# SCH_keyboard_ProMicro_2025-01-13.net
KiCad netlist of a schematic drawn in EasyEDA
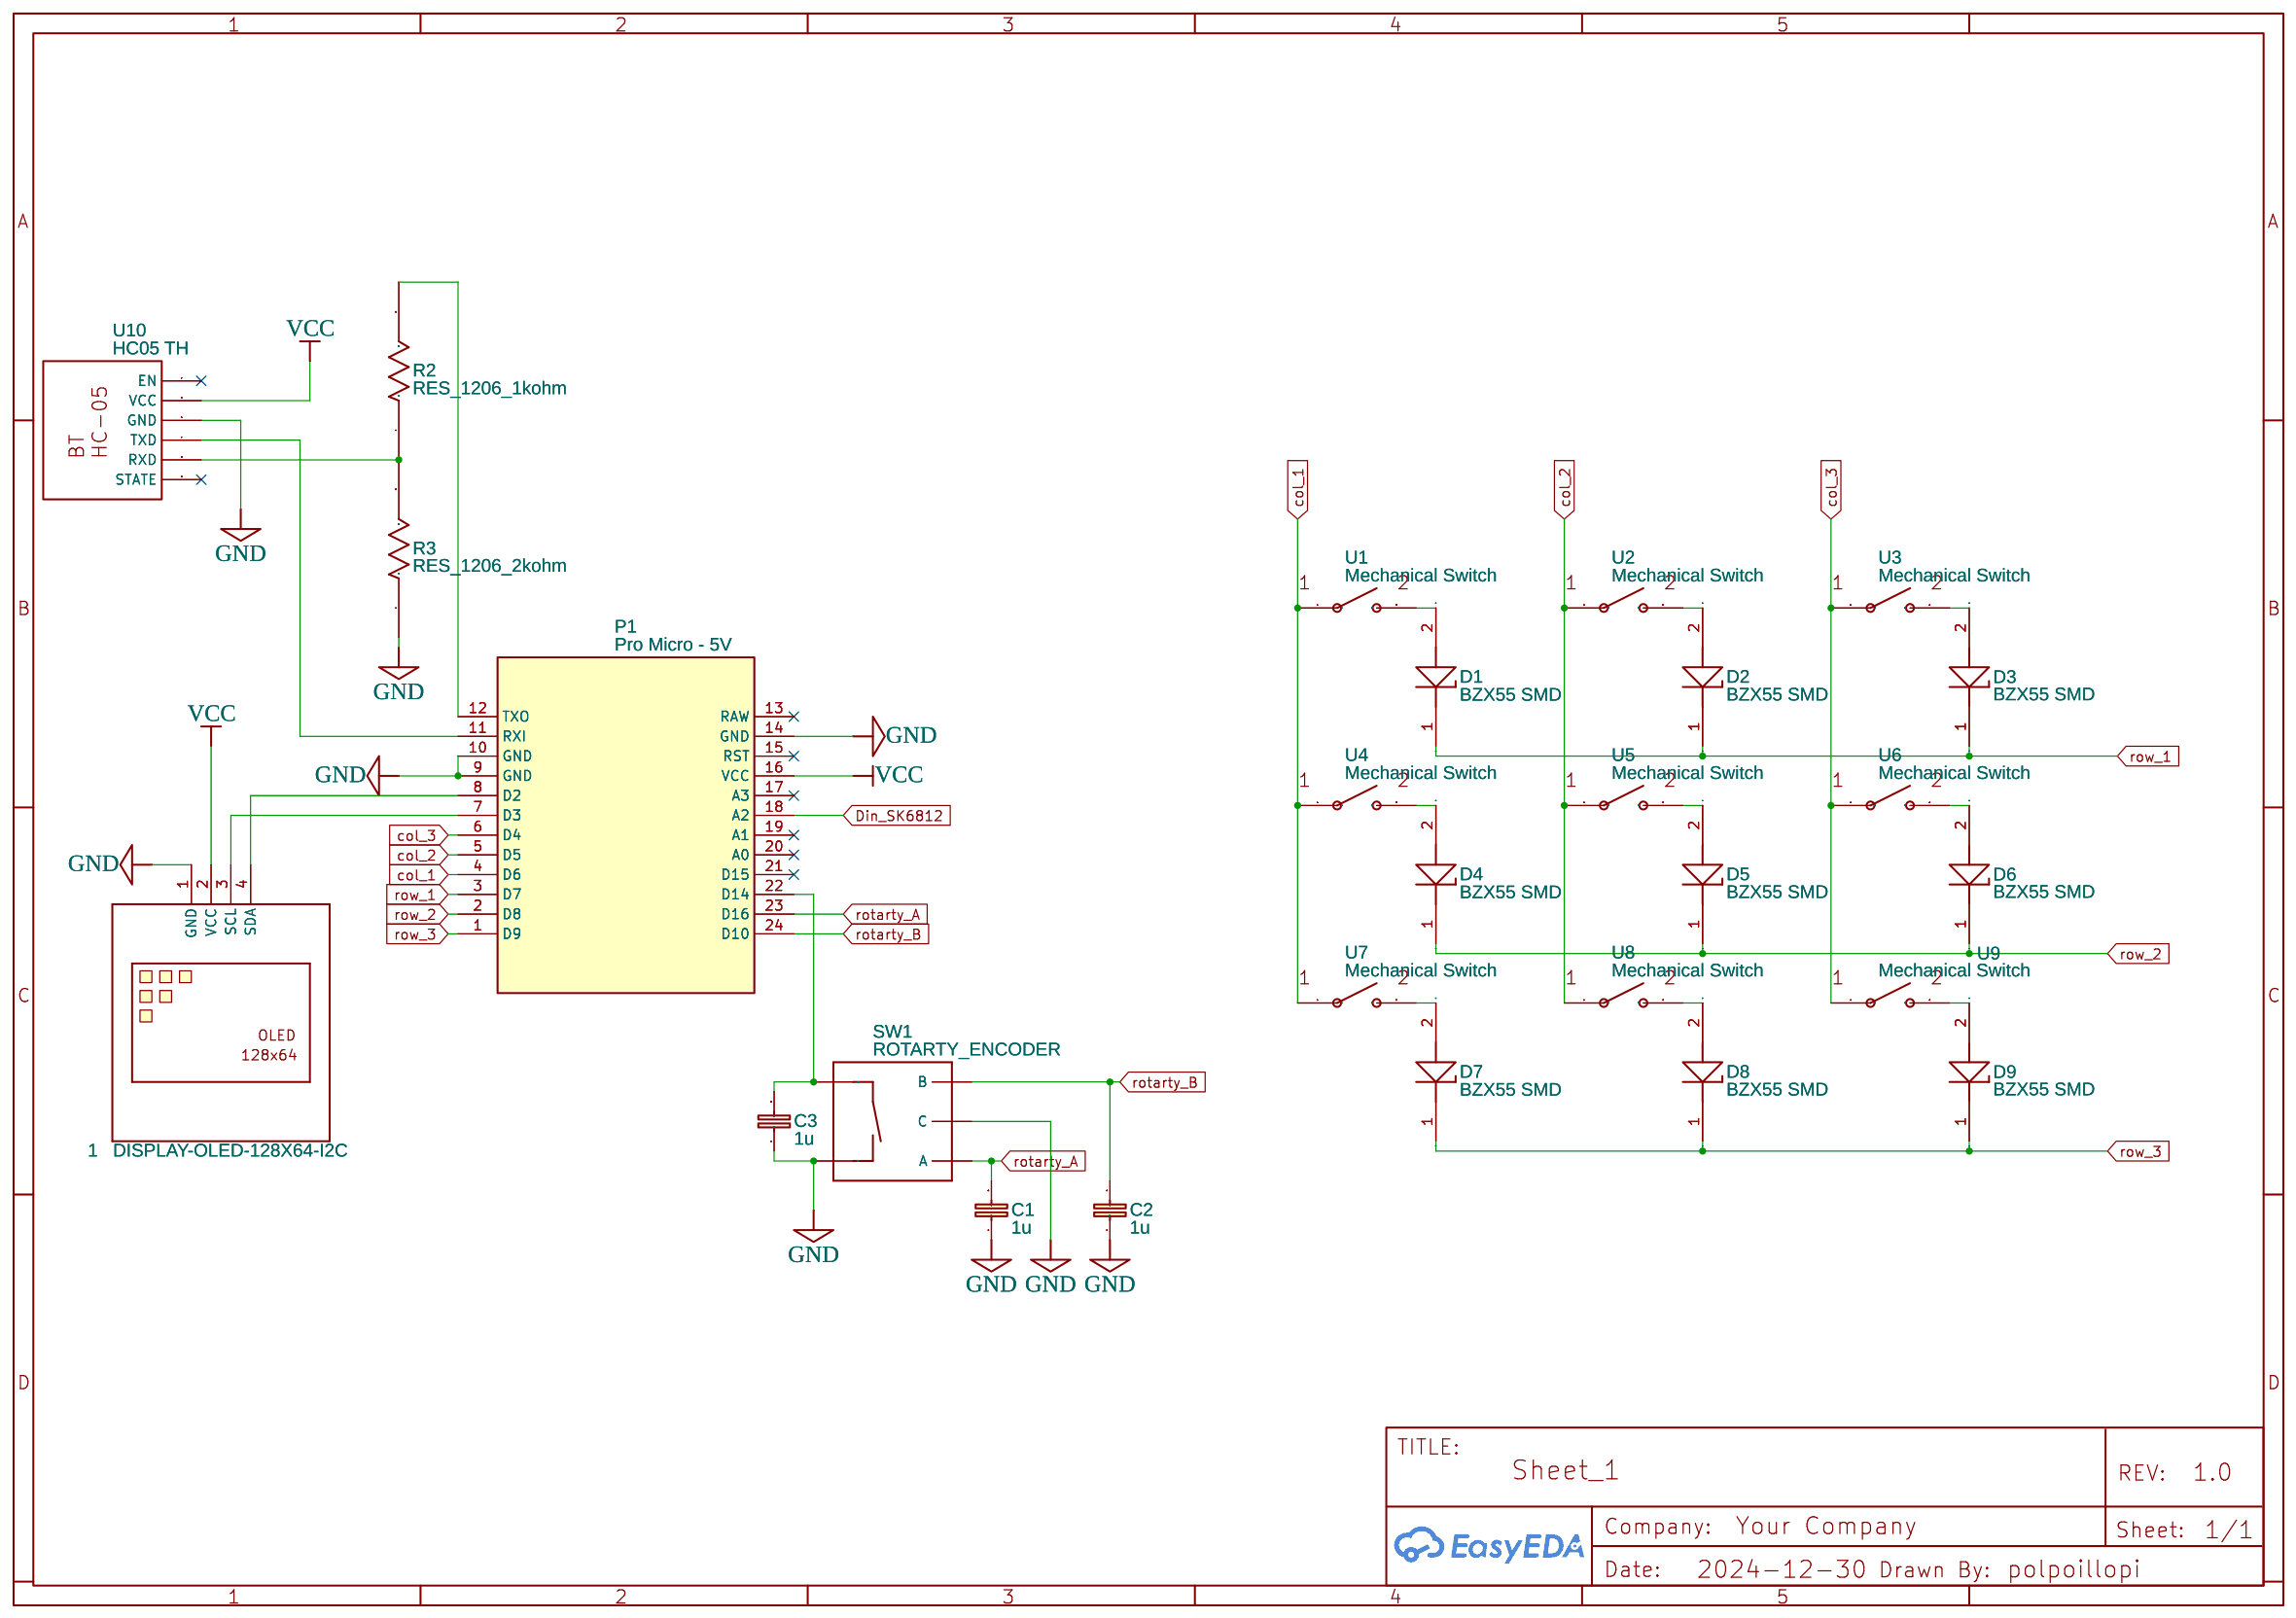
[diagram p0: Sheet_1]
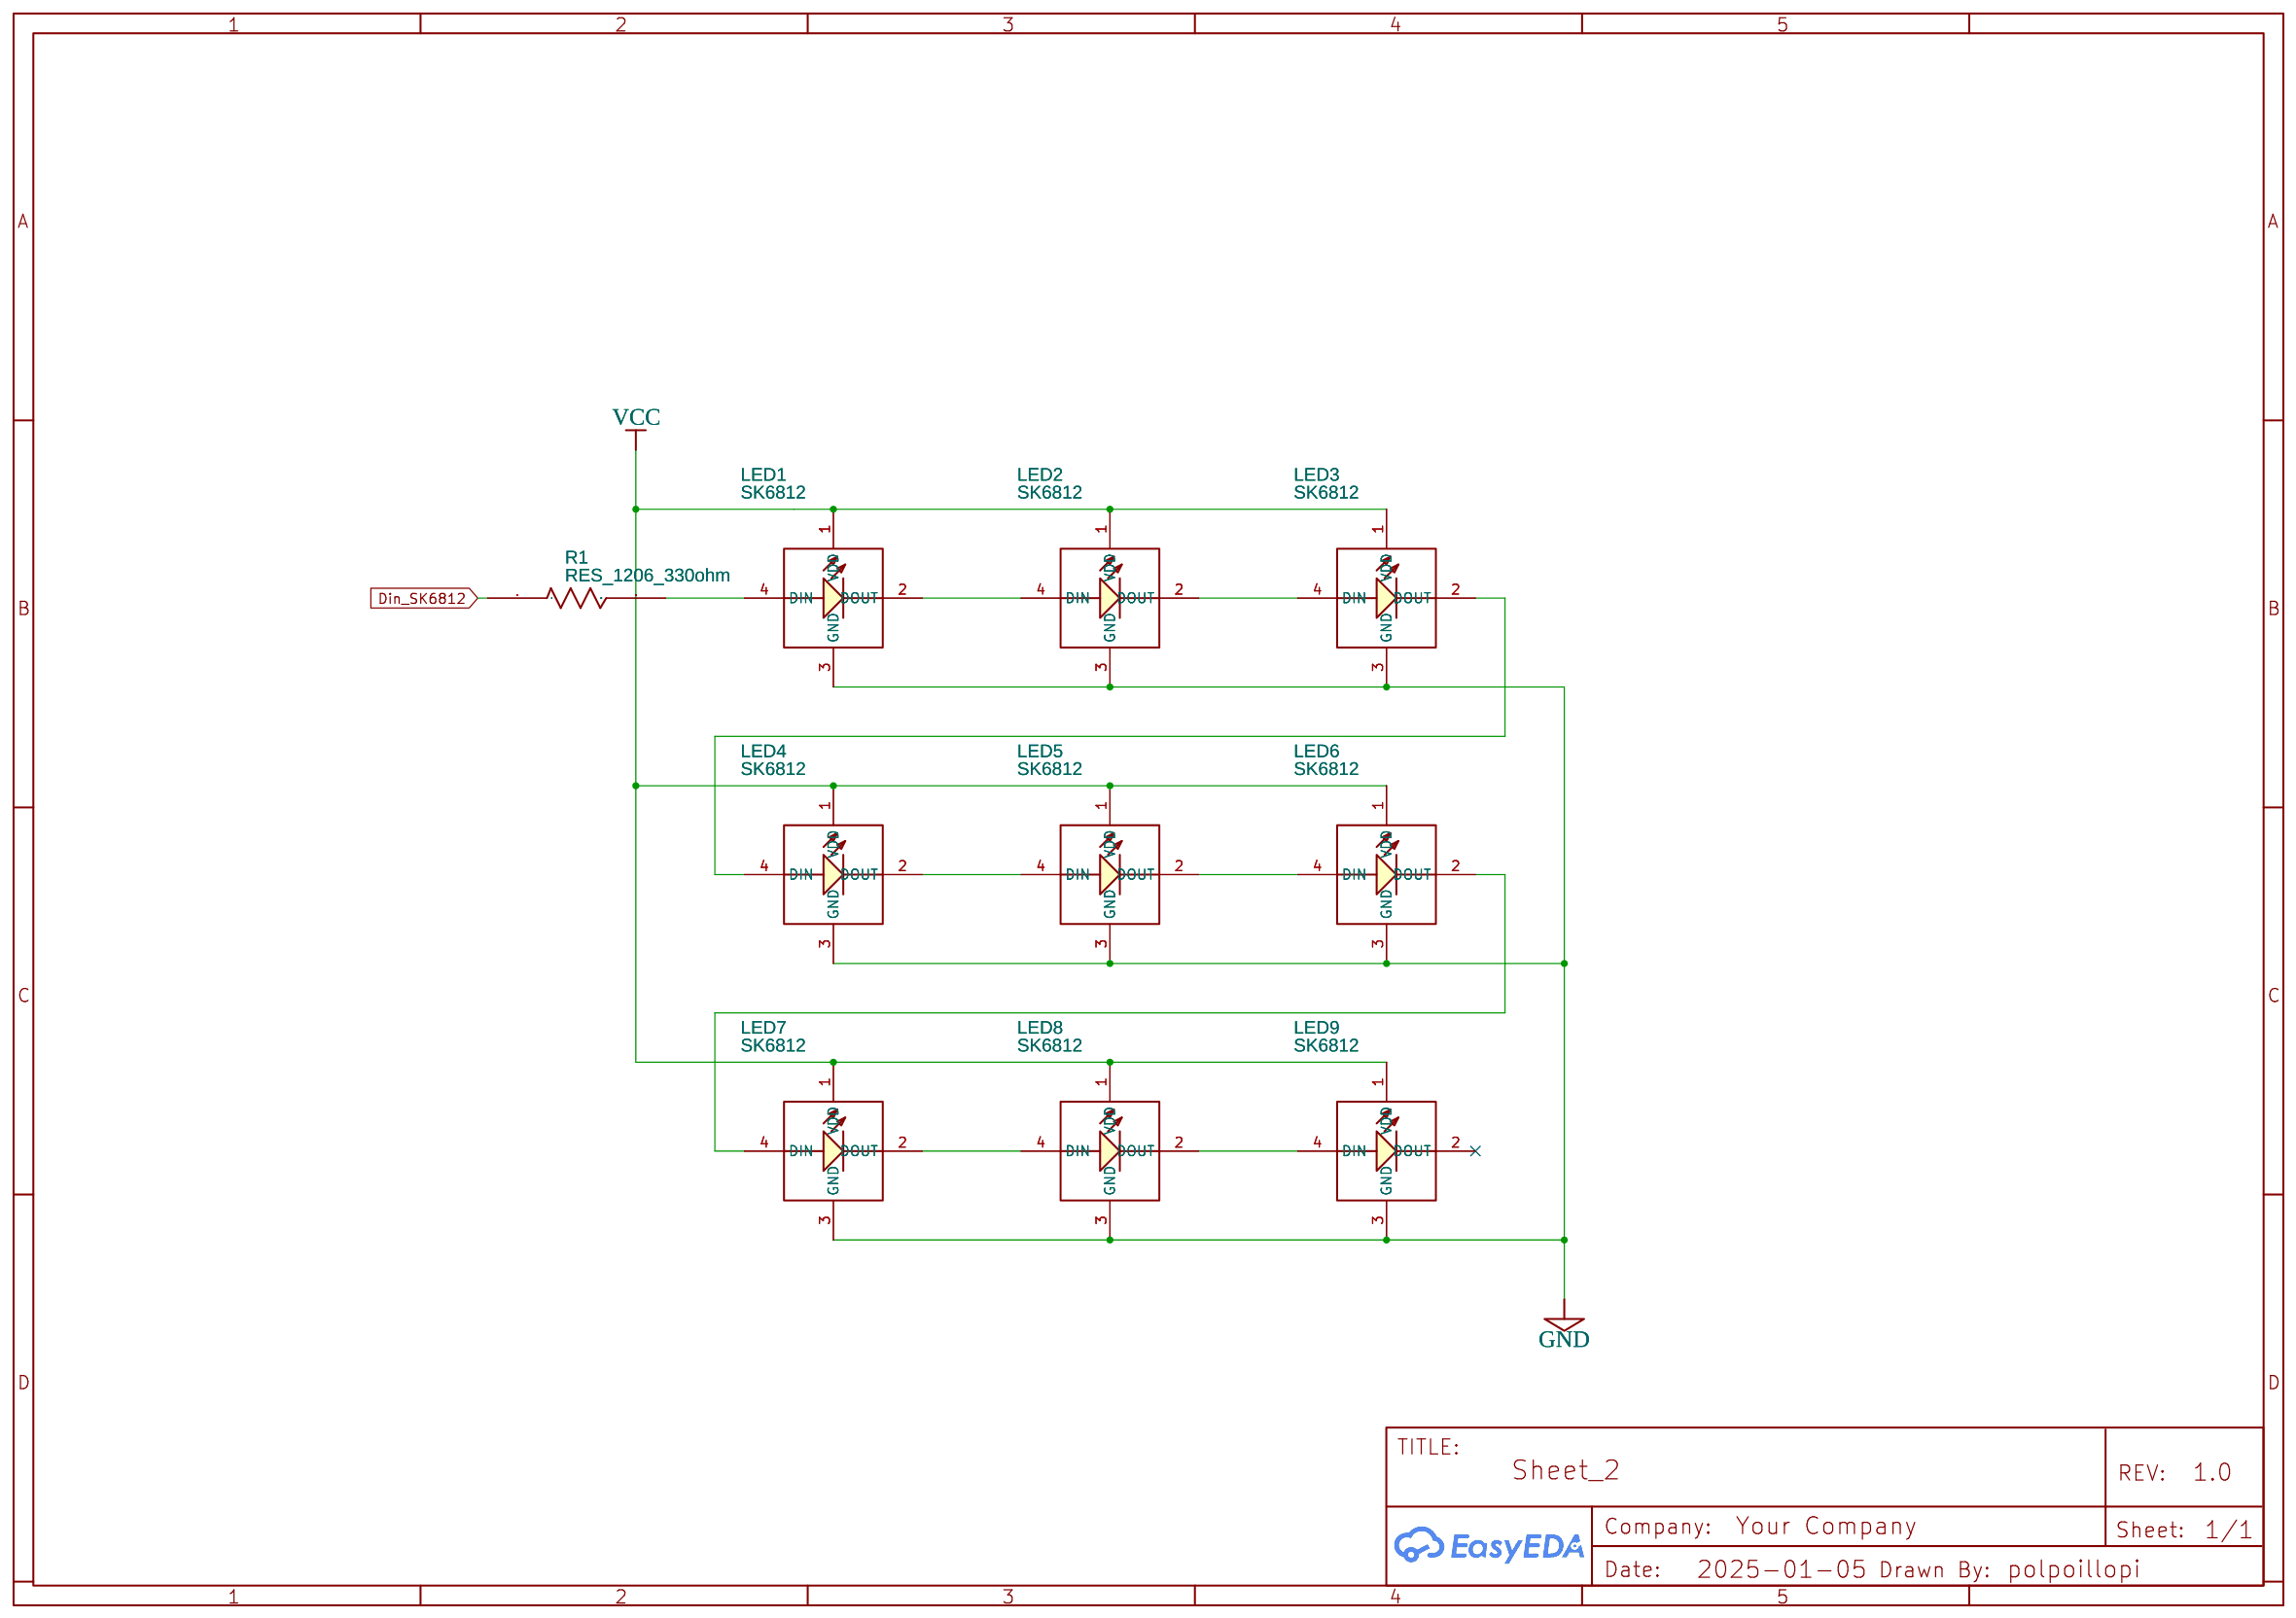
[diagram p1: Sheet_2]

(export (version "E")
  (design (tool "Eeschema 10.0.6"))
  (components
    (comp (ref "1") (value "DISPLAY-OLED-128X64-I2C") (libsource (lib "") (part "DISPLAY-OLED-128X64-I2C")))
    (comp (ref "C1") (value "1u") (libsource (lib "") (part "CAP1206")))
    (comp (ref "C2") (value "1u") (libsource (lib "") (part "CAP1206")))
    (comp (ref "C3") (value "1u") (libsource (lib "") (part "CAP1206")))
    (comp (ref "D1") (value "BZX55 SMD") (libsource (lib "") (part "BZX55 SMD")))
    (comp (ref "D2") (value "BZX55 SMD") (libsource (lib "") (part "BZX55 SMD")))
    (comp (ref "D3") (value "BZX55 SMD") (libsource (lib "") (part "BZX55 SMD")))
    (comp (ref "D4") (value "BZX55 SMD") (libsource (lib "") (part "BZX55 SMD")))
    (comp (ref "D5") (value "BZX55 SMD") (libsource (lib "") (part "BZX55 SMD")))
    (comp (ref "D6") (value "BZX55 SMD") (libsource (lib "") (part "BZX55 SMD")))
    (comp (ref "D7") (value "BZX55 SMD") (libsource (lib "") (part "BZX55 SMD")))
    (comp (ref "D8") (value "BZX55 SMD") (libsource (lib "") (part "BZX55 SMD")))
    (comp (ref "D9") (value "BZX55 SMD") (libsource (lib "") (part "BZX55 SMD")))
    (comp (ref "P1") (value "Pro Micro - 5V") (libsource (lib "") (part "Pro Micro - 5V")))
    (comp (ref "R2")
      (value "RES_1206_1kohm")
      (fields (field (name "Manufacturer") "Panasonic"))
      (libsource (lib "") (part "RES_1206_330K_5%"))
    )
    (comp (ref "R3")
      (value "RES_1206_2kohm")
      (fields (field (name "Manufacturer") "Panasonic"))
      (libsource (lib "") (part "RES_1206_330K_5%"))
    )
    (comp (ref "SW1") (value "ROTARTY_ENCODER") (libsource (lib "") (part "ROTARTY_ENCODER")))
    (comp (ref "U1")
      (value "Mechanical Switch")
      (libsource (lib "") (part "Cherry MX Mechanical Keyboard Switch"))
    )
    (comp (ref "U2")
      (value "Mechanical Switch")
      (libsource (lib "") (part "Cherry MX Mechanical Keyboard Switch"))
    )
    (comp (ref "U3")
      (value "Mechanical Switch")
      (libsource (lib "") (part "Cherry MX Mechanical Keyboard Switch"))
    )
    (comp (ref "U4")
      (value "Mechanical Switch")
      (libsource (lib "") (part "Cherry MX Mechanical Keyboard Switch"))
    )
    (comp (ref "U5")
      (value "Mechanical Switch")
      (libsource (lib "") (part "Cherry MX Mechanical Keyboard Switch"))
    )
    (comp (ref "U6")
      (value "Mechanical Switch")
      (libsource (lib "") (part "Cherry MX Mechanical Keyboard Switch"))
    )
    (comp (ref "U7")
      (value "Mechanical Switch")
      (libsource (lib "") (part "Cherry MX Mechanical Keyboard Switch"))
    )
    (comp (ref "U8")
      (value "Mechanical Switch")
      (libsource (lib "") (part "Cherry MX Mechanical Keyboard Switch"))
    )
    (comp (ref "U9")
      (value "Mechanical Switch")
      (libsource (lib "") (part "Cherry MX Mechanical Keyboard Switch"))
    )
    (comp (ref "U10") (value "HC05 TH") (libsource (lib "") (part "HC05 TH")))
    (comp (ref "LED1") (value "SK6812") (libsource (lib "") (part "SK6812")))
    (comp (ref "LED2") (value "SK6812") (libsource (lib "") (part "SK6812")))
    (comp (ref "LED3") (value "SK6812") (libsource (lib "") (part "SK6812")))
    (comp (ref "LED4") (value "SK6812") (libsource (lib "") (part "SK6812")))
    (comp (ref "LED5") (value "SK6812") (libsource (lib "") (part "SK6812")))
    (comp (ref "LED6") (value "SK6812") (libsource (lib "") (part "SK6812")))
    (comp (ref "LED7") (value "SK6812") (libsource (lib "") (part "SK6812")))
    (comp (ref "LED8") (value "SK6812") (libsource (lib "") (part "SK6812")))
    (comp (ref "LED9") (value "SK6812") (libsource (lib "") (part "SK6812")))
    (comp (ref "R1")
      (value "RES_1206_330ohm")
      (fields (field (name "Manufacturer") "Panasonic"))
      (libsource (lib "") (part "RES_1206_330K_5%"))
    )
  )
  (nets
    (net (code "1") (name "Din_SK6812") (class "Default")
      (node (ref "P1") (pin "18") (pinfunction "A2_18") (pintype "unspecified"))
      (node (ref "R1") (pin "A") (pinfunction "A_A") (pintype "unspecified"))
    )
    (net (code "2") (name "GND") (class "Default")
      (node (ref "1") (pin "1") (pinfunction "GND_1") (pintype "bidirectional"))
      (node (ref "C1") (pin "1") (pinfunction "1_1") (pintype "unspecified"))
      (node (ref "C2") (pin "1") (pinfunction "1_1") (pintype "unspecified"))
      (node (ref "C3") (pin "1") (pinfunction "1_1") (pintype "unspecified"))
      (node (ref "LED1") (pin "3") (pinfunction "GND_3") (pintype "unspecified"))
      (node (ref "LED2") (pin "3") (pinfunction "GND_3") (pintype "unspecified"))
      (node (ref "LED3") (pin "3") (pinfunction "GND_3") (pintype "unspecified"))
      (node (ref "LED4") (pin "3") (pinfunction "GND_3") (pintype "unspecified"))
      (node (ref "LED5") (pin "3") (pinfunction "GND_3") (pintype "unspecified"))
      (node (ref "LED6") (pin "3") (pinfunction "GND_3") (pintype "unspecified"))
      (node (ref "LED7") (pin "3") (pinfunction "GND_3") (pintype "unspecified"))
      (node (ref "LED8") (pin "3") (pinfunction "GND_3") (pintype "unspecified"))
      (node (ref "LED9") (pin "3") (pinfunction "GND_3") (pintype "unspecified"))
      (node (ref "P1") (pin "10") (pinfunction "GND_10") (pintype "unspecified"))
      (node (ref "P1") (pin "14") (pinfunction "GND_14") (pintype "unspecified"))
      (node (ref "P1") (pin "9") (pinfunction "GND_9") (pintype "unspecified"))
      (node (ref "R3") (pin "A") (pinfunction "A_A") (pintype "unspecified"))
      (node (ref "SW1") (pin "2") (pinfunction "C_2") (pintype "unspecified"))
      (node (ref "SW1") (pin "5") (pinfunction "SW-_5") (pintype "unspecified"))
      (node (ref "U10") (pin "3") (pinfunction "GND_3") (pintype "unspecified"))
    )
    (net (code "3") (name "Net-(1-SCL)") (class "Default")
      (node (ref "1") (pin "3") (pinfunction "SCL_3") (pintype "bidirectional"))
      (node (ref "P1") (pin "7") (pinfunction "D3_7") (pintype "unspecified"))
    )
    (net (code "4") (name "Net-(1-SDA)") (class "Default")
      (node (ref "1") (pin "4") (pinfunction "SDA_4") (pintype "bidirectional"))
      (node (ref "P1") (pin "8") (pinfunction "D2_8") (pintype "unspecified"))
    )
    (net (code "5") (name "Net-(D1-K)") (class "Default")
      (node (ref "D1") (pin "2") (pinfunction "K_2") (pintype "unspecified"))
      (node (ref "U1") (pin "2") (pinfunction "2_2") (pintype "unspecified"))
    )
    (net (code "6") (name "Net-(D2-K)") (class "Default")
      (node (ref "D2") (pin "2") (pinfunction "K_2") (pintype "unspecified"))
      (node (ref "U2") (pin "2") (pinfunction "2_2") (pintype "unspecified"))
    )
    (net (code "7") (name "Net-(D3-K)") (class "Default")
      (node (ref "D3") (pin "2") (pinfunction "K_2") (pintype "unspecified"))
      (node (ref "U3") (pin "2") (pinfunction "2_2") (pintype "unspecified"))
    )
    (net (code "8") (name "Net-(D4-K)") (class "Default")
      (node (ref "D4") (pin "2") (pinfunction "K_2") (pintype "unspecified"))
      (node (ref "U4") (pin "2") (pinfunction "2_2") (pintype "unspecified"))
    )
    (net (code "9") (name "Net-(D5-K)") (class "Default")
      (node (ref "D5") (pin "2") (pinfunction "K_2") (pintype "unspecified"))
      (node (ref "U5") (pin "2") (pinfunction "2_2") (pintype "unspecified"))
    )
    (net (code "10") (name "Net-(D6-K)") (class "Default")
      (node (ref "D6") (pin "2") (pinfunction "K_2") (pintype "unspecified"))
      (node (ref "U6") (pin "2") (pinfunction "2_2") (pintype "unspecified"))
    )
    (net (code "11") (name "Net-(D7-K)") (class "Default")
      (node (ref "D7") (pin "2") (pinfunction "K_2") (pintype "unspecified"))
      (node (ref "U7") (pin "2") (pinfunction "2_2") (pintype "unspecified"))
    )
    (net (code "12") (name "Net-(D8-K)") (class "Default")
      (node (ref "D8") (pin "2") (pinfunction "K_2") (pintype "unspecified"))
      (node (ref "U8") (pin "2") (pinfunction "2_2") (pintype "unspecified"))
    )
    (net (code "13") (name "Net-(D9-K)") (class "Default")
      (node (ref "D9") (pin "2") (pinfunction "K_2") (pintype "unspecified"))
      (node (ref "U9") (pin "2") (pinfunction "2_2") (pintype "unspecified"))
    )
    (net (code "14") (name "Net-(LED1-DIN)") (class "Default")
      (node (ref "LED1") (pin "4") (pinfunction "DIN_4") (pintype "unspecified"))
      (node (ref "R1") (pin "B") (pinfunction "B_B") (pintype "unspecified"))
    )
    (net (code "15") (name "Net-(LED1-DOUT)") (class "Default")
      (node (ref "LED1") (pin "2") (pinfunction "DOUT_2") (pintype "unspecified"))
      (node (ref "LED2") (pin "4") (pinfunction "DIN_4") (pintype "unspecified"))
    )
    (net (code "16") (name "Net-(LED2-DOUT)") (class "Default")
      (node (ref "LED2") (pin "2") (pinfunction "DOUT_2") (pintype "unspecified"))
      (node (ref "LED3") (pin "4") (pinfunction "DIN_4") (pintype "unspecified"))
    )
    (net (code "17") (name "Net-(LED3-DOUT)") (class "Default")
      (node (ref "LED3") (pin "2") (pinfunction "DOUT_2") (pintype "unspecified"))
      (node (ref "LED4") (pin "4") (pinfunction "DIN_4") (pintype "unspecified"))
    )
    (net (code "18") (name "Net-(LED4-DOUT)") (class "Default")
      (node (ref "LED4") (pin "2") (pinfunction "DOUT_2") (pintype "unspecified"))
      (node (ref "LED5") (pin "4") (pinfunction "DIN_4") (pintype "unspecified"))
    )
    (net (code "19") (name "Net-(LED5-DOUT)") (class "Default")
      (node (ref "LED5") (pin "2") (pinfunction "DOUT_2") (pintype "unspecified"))
      (node (ref "LED6") (pin "4") (pinfunction "DIN_4") (pintype "unspecified"))
    )
    (net (code "20") (name "Net-(LED6-DOUT)") (class "Default")
      (node (ref "LED6") (pin "2") (pinfunction "DOUT_2") (pintype "unspecified"))
      (node (ref "LED7") (pin "4") (pinfunction "DIN_4") (pintype "unspecified"))
    )
    (net (code "21") (name "Net-(LED7-DOUT)") (class "Default")
      (node (ref "LED7") (pin "2") (pinfunction "DOUT_2") (pintype "unspecified"))
      (node (ref "LED8") (pin "4") (pinfunction "DIN_4") (pintype "unspecified"))
    )
    (net (code "22") (name "Net-(LED8-DOUT)") (class "Default")
      (node (ref "LED8") (pin "2") (pinfunction "DOUT_2") (pintype "unspecified"))
      (node (ref "LED9") (pin "4") (pinfunction "DIN_4") (pintype "unspecified"))
    )
    (net (code "23") (name "Net-(P1-D14)") (class "Default")
      (node (ref "C3") (pin "2") (pinfunction "2_2") (pintype "unspecified"))
      (node (ref "P1") (pin "22") (pinfunction "D14_22") (pintype "unspecified"))
      (node (ref "SW1") (pin "4") (pinfunction "SW+_4") (pintype "unspecified"))
    )
    (net (code "24") (name "Net-(P1-RXI)") (class "Default")
      (node (ref "P1") (pin "11") (pinfunction "RXI_11") (pintype "unspecified"))
      (node (ref "U10") (pin "4") (pinfunction "TXD_4") (pintype "unspecified"))
    )
    (net (code "25") (name "Net-(P1-TXO)") (class "Default")
      (node (ref "P1") (pin "12") (pinfunction "TXO_12") (pintype "unspecified"))
      (node (ref "R2") (pin "B") (pinfunction "B_B") (pintype "unspecified"))
    )
    (net (code "26") (name "Net-(U10-RXD)") (class "Default")
      (node (ref "R2") (pin "A") (pinfunction "A_A") (pintype "unspecified"))
      (node (ref "R3") (pin "B") (pinfunction "B_B") (pintype "unspecified"))
      (node (ref "U10") (pin "5") (pinfunction "RXD_5") (pintype "unspecified"))
    )
    (net (code "27") (name "VCC") (class "Default")
      (node (ref "1") (pin "2") (pinfunction "VCC_2") (pintype "bidirectional"))
      (node (ref "LED1") (pin "1") (pinfunction "VDD_1") (pintype "unspecified"))
      (node (ref "LED2") (pin "1") (pinfunction "VDD_1") (pintype "unspecified"))
      (node (ref "LED3") (pin "1") (pinfunction "VDD_1") (pintype "unspecified"))
      (node (ref "LED4") (pin "1") (pinfunction "VDD_1") (pintype "unspecified"))
      (node (ref "LED5") (pin "1") (pinfunction "VDD_1") (pintype "unspecified"))
      (node (ref "LED6") (pin "1") (pinfunction "VDD_1") (pintype "unspecified"))
      (node (ref "LED7") (pin "1") (pinfunction "VDD_1") (pintype "unspecified"))
      (node (ref "LED8") (pin "1") (pinfunction "VDD_1") (pintype "unspecified"))
      (node (ref "LED9") (pin "1") (pinfunction "VDD_1") (pintype "unspecified"))
      (node (ref "P1") (pin "16") (pinfunction "VCC_16") (pintype "unspecified"))
      (node (ref "U10") (pin "2") (pinfunction "VCC_2") (pintype "unspecified"))
    )
    (net (code "28") (name "col_1") (class "Default")
      (node (ref "P1") (pin "4") (pinfunction "D6_4") (pintype "unspecified"))
      (node (ref "U1") (pin "1") (pinfunction "1_1") (pintype "unspecified"))
      (node (ref "U4") (pin "1") (pinfunction "1_1") (pintype "unspecified"))
      (node (ref "U7") (pin "1") (pinfunction "1_1") (pintype "unspecified"))
    )
    (net (code "29") (name "col_2") (class "Default")
      (node (ref "P1") (pin "5") (pinfunction "D5_5") (pintype "unspecified"))
      (node (ref "U2") (pin "1") (pinfunction "1_1") (pintype "unspecified"))
      (node (ref "U5") (pin "1") (pinfunction "1_1") (pintype "unspecified"))
      (node (ref "U8") (pin "1") (pinfunction "1_1") (pintype "unspecified"))
    )
    (net (code "30") (name "col_3") (class "Default")
      (node (ref "P1") (pin "6") (pinfunction "D4_6") (pintype "unspecified"))
      (node (ref "U3") (pin "1") (pinfunction "1_1") (pintype "unspecified"))
      (node (ref "U6") (pin "1") (pinfunction "1_1") (pintype "unspecified"))
      (node (ref "U9") (pin "1") (pinfunction "1_1") (pintype "unspecified"))
    )
    (net (code "31") (name "rotarty_A") (class "Default")
      (node (ref "C1") (pin "2") (pinfunction "2_2") (pintype "unspecified"))
      (node (ref "P1") (pin "23") (pinfunction "D16_23") (pintype "unspecified"))
      (node (ref "SW1") (pin "1") (pinfunction "A_1") (pintype "unspecified"))
    )
    (net (code "32") (name "rotarty_B") (class "Default")
      (node (ref "C2") (pin "2") (pinfunction "2_2") (pintype "unspecified"))
      (node (ref "P1") (pin "24") (pinfunction "D10_24") (pintype "unspecified"))
      (node (ref "SW1") (pin "3") (pinfunction "B_3") (pintype "unspecified"))
    )
    (net (code "33") (name "row_1") (class "Default")
      (node (ref "D1") (pin "1") (pinfunction "A_1") (pintype "unspecified"))
      (node (ref "D2") (pin "1") (pinfunction "A_1") (pintype "unspecified"))
      (node (ref "D3") (pin "1") (pinfunction "A_1") (pintype "unspecified"))
      (node (ref "P1") (pin "3") (pinfunction "D7_3") (pintype "unspecified"))
    )
    (net (code "34") (name "row_2") (class "Default")
      (node (ref "D4") (pin "1") (pinfunction "A_1") (pintype "unspecified"))
      (node (ref "D5") (pin "1") (pinfunction "A_1") (pintype "unspecified"))
      (node (ref "D6") (pin "1") (pinfunction "A_1") (pintype "unspecified"))
      (node (ref "P1") (pin "2") (pinfunction "D8_2") (pintype "unspecified"))
    )
    (net (code "35") (name "row_3") (class "Default")
      (node (ref "D7") (pin "1") (pinfunction "A_1") (pintype "unspecified"))
      (node (ref "D8") (pin "1") (pinfunction "A_1") (pintype "unspecified"))
      (node (ref "D9") (pin "1") (pinfunction "A_1") (pintype "unspecified"))
      (node (ref "P1") (pin "1") (pinfunction "D9_1") (pintype "unspecified"))
    )
    (net (code "36") (name "unconnected-(LED9-DOUT-Pad2)") (class "Default")
      (node (ref "LED9") (pin "2") (pinfunction "DOUT_2") (pintype "unspecified+no_connect"))
    )
    (net (code "37") (name "unconnected-(P1-A0-Pad20)") (class "Default")
      (node (ref "P1") (pin "20") (pinfunction "A0_20") (pintype "unspecified+no_connect"))
    )
    (net (code "38") (name "unconnected-(P1-A1-Pad19)") (class "Default")
      (node (ref "P1") (pin "19") (pinfunction "A1_19") (pintype "unspecified+no_connect"))
    )
    (net (code "39") (name "unconnected-(P1-A3-Pad17)") (class "Default")
      (node (ref "P1") (pin "17") (pinfunction "A3_17") (pintype "unspecified+no_connect"))
    )
    (net (code "40") (name "unconnected-(P1-D15-Pad21)") (class "Default")
      (node (ref "P1") (pin "21") (pinfunction "D15_21") (pintype "unspecified+no_connect"))
    )
    (net (code "41") (name "unconnected-(P1-RAW-Pad13)") (class "Default")
      (node (ref "P1") (pin "13") (pinfunction "RAW_13") (pintype "unspecified+no_connect"))
    )
    (net (code "42") (name "unconnected-(P1-RST-Pad15)") (class "Default")
      (node (ref "P1") (pin "15") (pinfunction "RST_15") (pintype "unspecified+no_connect"))
    )
    (net (code "43") (name "unconnected-(U10-EN-Pad1)") (class "Default")
      (node (ref "U10") (pin "1") (pinfunction "EN_1") (pintype "unspecified+no_connect"))
    )
    (net (code "44") (name "unconnected-(U10-STATE-Pad6)") (class "Default")
      (node (ref "U10") (pin "6") (pinfunction "STATE_6") (pintype "unspecified+no_connect"))
    )
  )
)
